# AuxBoard030610.net
KiCad netlist of a schematic drawn in Altium Designer
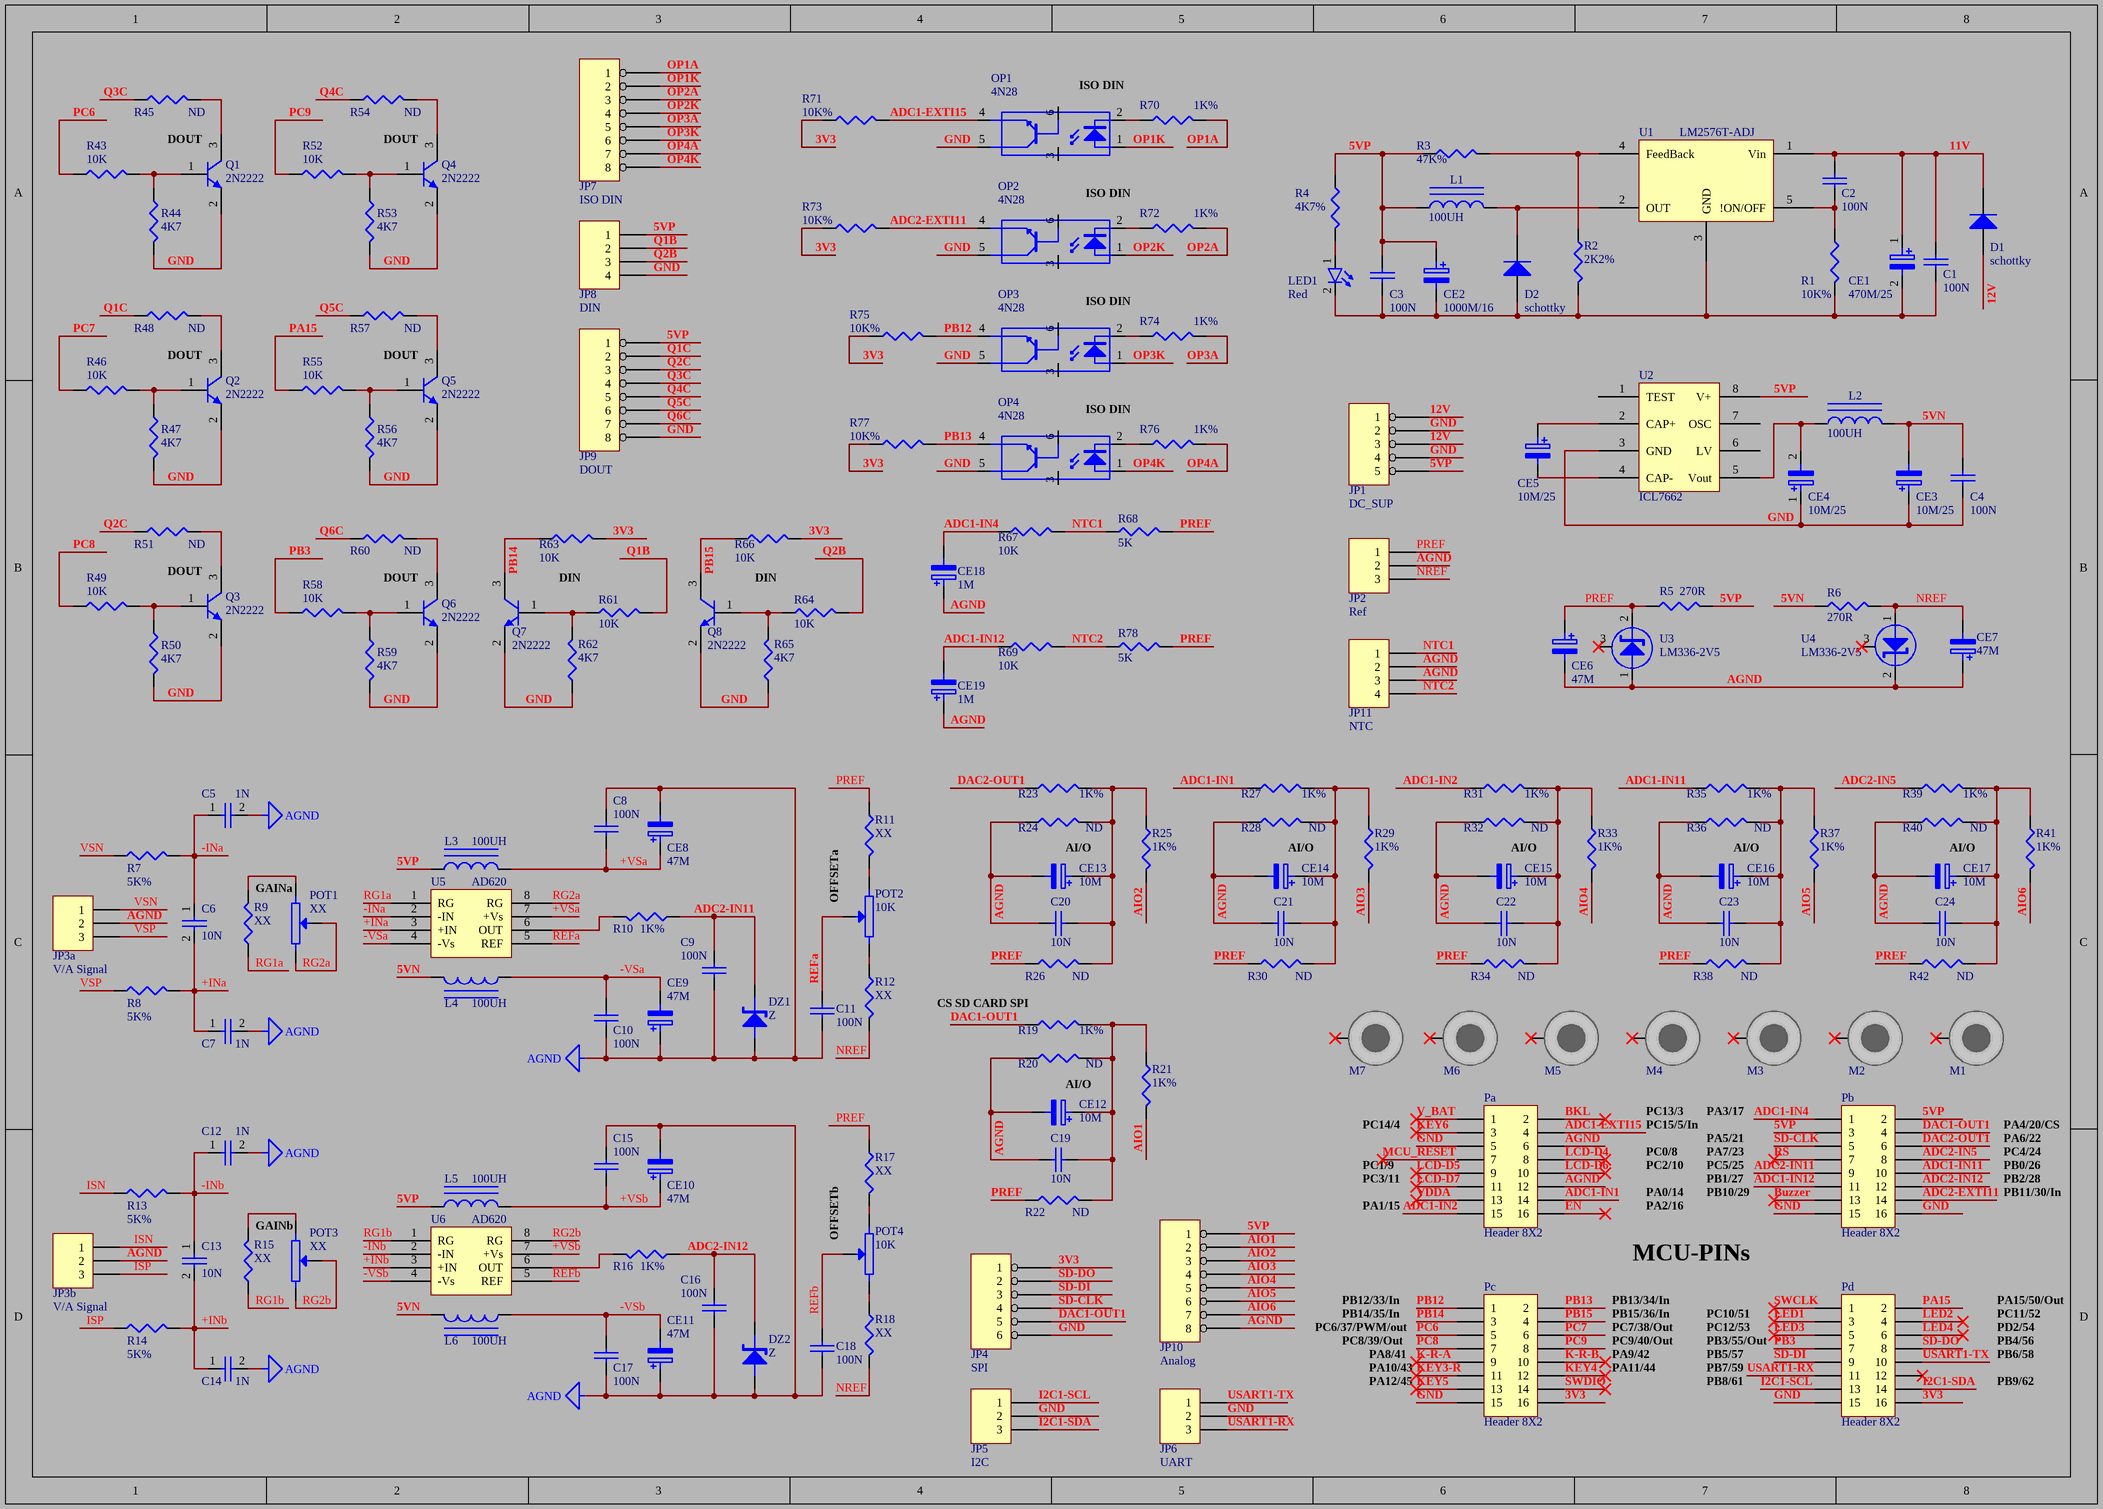
[diagram p0: AuxBoard030610.SchDoc]

(export (version "E")
  (design (tool "Eeschema 10.0.6"))
  (components
    (comp (ref "C1") (value "100N") (footprint "C2P") (libsource (lib "*") (part "C")))
    (comp (ref "C2") (value "100N") (footprint "SMD_CAP_1206.") (libsource (lib "*") (part "C")))
    (comp (ref "C3") (value "100N") (footprint "SMD_CAP_1206.") (libsource (lib "*") (part "C")))
    (comp (ref "C4") (value "100N") (footprint "SMD_CAP_1206.") (libsource (lib "*") (part "C")))
    (comp (ref "C5") (value "1N") (footprint "SMD_CAP_1206.") (libsource (lib "1402 Schlib 2020") (part "C")))
    (comp (ref "C6")
      (value "10N")
      (footprint "SMD_CAP_1206.")
      (libsource (lib "1402 Schlib 2020") (part "C"))
    )
    (comp (ref "C7") (value "1N") (footprint "SMD_CAP_1206.") (libsource (lib "1402 Schlib 2020") (part "C")))
    (comp (ref "C8")
      (value "100N")
      (footprint "SMD_CAP_1206.")
      (libsource (lib "1403 Schlib 2020") (part "C"))
    )
    (comp (ref "C9")
      (value "100N")
      (footprint "SMD_CAP_1206.")
      (libsource (lib "1403 Schlib 2020") (part "C"))
    )
    (comp (ref "C10")
      (value "100N")
      (footprint "SMD_CAP_1206.")
      (libsource (lib "1403 Schlib 2020") (part "C"))
    )
    (comp (ref "C11")
      (value "100N")
      (footprint "SMD_CAP_1206.")
      (libsource (lib "1403 Schlib 2020") (part "C"))
    )
    (comp (ref "C12")
      (value "1N")
      (footprint "SMD_CAP_1206.")
      (libsource (lib "1402 Schlib 2020") (part "C"))
    )
    (comp (ref "C13")
      (value "10N")
      (footprint "SMD_CAP_1206.")
      (libsource (lib "1402 Schlib 2020") (part "C"))
    )
    (comp (ref "C14")
      (value "1N")
      (footprint "SMD_CAP_1206.")
      (libsource (lib "1402 Schlib 2020") (part "C"))
    )
    (comp (ref "C15")
      (value "100N")
      (footprint "SMD_CAP_1206.")
      (libsource (lib "1403 Schlib 2020") (part "C"))
    )
    (comp (ref "C16")
      (value "100N")
      (footprint "SMD_CAP_1206.")
      (libsource (lib "1403 Schlib 2020") (part "C"))
    )
    (comp (ref "C17")
      (value "100N")
      (footprint "SMD_CAP_1206.")
      (libsource (lib "1403 Schlib 2020") (part "C"))
    )
    (comp (ref "C18")
      (value "100N")
      (footprint "SMD_CAP_1206.")
      (libsource (lib "1403 Schlib 2020") (part "C"))
    )
    (comp (ref "C19") (value "10N") (footprint "SMD_CAP_1206.") (libsource (lib "*") (part "C")))
    (comp (ref "C20") (value "10N") (footprint "SMD_CAP_1206.") (libsource (lib "*") (part "C")))
    (comp (ref "C21") (value "10N") (footprint "SMD_CAP_1206.") (libsource (lib "*") (part "C")))
    (comp (ref "C22") (value "10N") (footprint "SMD_CAP_1206.") (libsource (lib "*") (part "C")))
    (comp (ref "C23") (value "10N") (footprint "SMD_CAP_1206.") (libsource (lib "*") (part "C")))
    (comp (ref "C24") (value "10N") (footprint "SMD_CAP_1206.") (libsource (lib "*") (part "C")))
    (comp (ref "CE1") (value "470M/25") (footprint "CAP-E-6") (libsource (lib "") (part "E_1")))
    (comp (ref "CE2") (value "1000M/16") (footprint "CAP-E-6") (libsource (lib "*") (part "E")))
    (comp (ref "CE3") (value "10M/25") (footprint "CAP-E-3") (libsource (lib "*") (part "E")))
    (comp (ref "CE4") (value "10M/25") (footprint "CAP-E-3") (libsource (lib "") (part "E_1")))
    (comp (ref "CE5") (value "10M/25") (footprint "CAP-E-3") (libsource (lib "*") (part "E")))
    (comp (ref "CE6") (value "47M") (footprint "CAP-E-4") (libsource (lib "1403 Schlib 2020") (part "E")))
    (comp (ref "CE7") (value "47M") (footprint "CAP-E-4") (libsource (lib "1403 Schlib 2020") (part "E")))
    (comp (ref "CE8") (value "47M") (footprint "CAP-E-4") (libsource (lib "1403 Schlib 2020") (part "E")))
    (comp (ref "CE9") (value "47M") (footprint "CAP-E-4") (libsource (lib "1403 Schlib 2020") (part "E")))
    (comp (ref "CE10") (value "47M") (footprint "CAP-E-4") (libsource (lib "1403 Schlib 2020") (part "E")))
    (comp (ref "CE11") (value "47M") (footprint "CAP-E-4") (libsource (lib "1403 Schlib 2020") (part "E")))
    (comp (ref "CE12") (value "10M") (footprint "CAP-E-3") (libsource (lib "*") (part "E")))
    (comp (ref "CE13") (value "10M") (footprint "CAP-E-3") (libsource (lib "*") (part "E")))
    (comp (ref "CE14") (value "10M") (footprint "CAP-E-3") (libsource (lib "*") (part "E")))
    (comp (ref "CE15") (value "10M") (footprint "CAP-E-3") (libsource (lib "*") (part "E")))
    (comp (ref "CE16") (value "10M") (footprint "CAP-E-3") (libsource (lib "*") (part "E")))
    (comp (ref "CE17") (value "10M") (footprint "CAP-E-3") (libsource (lib "*") (part "E")))
    (comp (ref "CE18") (value "1M") (footprint "CAP-E-2") (libsource (lib "*") (part "E")))
    (comp (ref "CE19") (value "1M") (footprint "CAP-E-2") (libsource (lib "*") (part "E")))
    (comp (ref "D1")
      (value "schottky")
      (footprint "SMA-M")
      (description "Default Diode")
      (fields (field (name "PUBLISHER") "Altium Limited"))
      (libsource (lib "Miscellaneous Devices") (part "Diode"))
    )
    (comp (ref "D2")
      (value "schottky")
      (footprint "SMA-M")
      (description "Default Diode")
      (fields (field (name "PUBLISHER") "Altium Limited"))
      (libsource (lib "Miscellaneous Devices") (part "Diode"))
    )
    (comp (ref "DZ1") (value "Z") (footprint "D4P") (libsource (lib "1402 Schlib 2020") (part "Z")))
    (comp (ref "DZ2") (value "Z") (footprint "D4P") (libsource (lib "1402 Schlib 2020") (part "Z")))
    (comp (ref "JP1")
      (value "DC_SUP")
      (footprint "dsip 5 right")
      (libsource (lib "1402 Schlib 2020") (part "HEADER 5"))
    )
    (comp (ref "JP2")
      (value "Ref")
      (footprint "dsip 3 right")
      (description "Header, 3-Pin")
      (fields (field (name "PUBLISHER") "Altium Limited"))
      (libsource (lib "1402 Schlib 2020") (part "Header 3"))
    )
    (comp (ref "JP3a")
      (value "V/A Signal")
      (footprint "dsip 3 right")
      (description "Header, 3-Pin")
      (fields (field (name "PUBLISHER") "Altium Limited"))
      (libsource (lib "1402 Schlib 2020") (part "Header 3"))
    )
    (comp (ref "JP3b")
      (value "V/A Signal")
      (footprint "dsip 3 right")
      (description "Header, 3-Pin")
      (fields (field (name "PUBLISHER") "Altium Limited"))
      (libsource (lib "1402 Schlib 2020") (part "Header 3"))
    )
    (comp (ref "JP4")
      (value "SPI")
      (footprint "SIP 6 Right")
      (libsource (lib "1402 Schlib 2020") (part "HEADER 6"))
    )
    (comp (ref "JP5")
      (value "I2C")
      (footprint "SIP 3 Right")
      (description "Header, 3-Pin")
      (fields (field (name "PUBLISHER") "Altium Limited"))
      (libsource (lib "1402 Schlib 2020") (part "Header 3"))
    )
    (comp (ref "JP6")
      (value "UART")
      (footprint "SIP 3 Right")
      (description "Header, 3-Pin")
      (fields (field (name "PUBLISHER") "Altium Limited"))
      (libsource (lib "1402 Schlib 2020") (part "Header 3"))
    )
    (comp (ref "JP7")
      (value "ISO DIN")
      (footprint "dsip 8 right")
      (libsource (lib "1402 Schlib 2020") (part "HEADER 8"))
    )
    (comp (ref "JP8")
      (value "DIN")
      (footprint "dsip 4 right")
      (description "Header, 4-Pin")
      (fields (field (name "PUBLISHER") "Altium Limited"))
      (libsource (lib "1402 Schlib 2020") (part "Header 4"))
    )
    (comp (ref "JP9")
      (value "DOUT")
      (footprint "dsip 8 right")
      (libsource (lib "1402 Schlib 2020") (part "HEADER 8"))
    )
    (comp (ref "JP10")
      (value "Analog")
      (footprint "dsip 8 right")
      (libsource (lib "1402 Schlib 2020") (part "HEADER 8"))
    )
    (comp (ref "JP11")
      (value "NTC")
      (footprint "dsip 4 right")
      (description "Header, 4-Pin")
      (fields (field (name "PUBLISHER") "Altium Limited"))
      (libsource (lib "1402 Schlib 2020") (part "Header 4"))
    )
    (comp (ref "L1") (value "100UH") (footprint "INDUCTOR-ylw") (libsource (lib "") (part "INDUCTOR IRON_1")))
    (comp (ref "L2") (value "100UH") (footprint "r4p") (libsource (lib "") (part "INDUCTOR IRON_1")))
    (comp (ref "L3") (value "100UH") (footprint "r4p") (libsource (lib "") (part "INDUCTOR IRON_1")))
    (comp (ref "L4") (value "100UH") (footprint "r4p") (libsource (lib "*") (part "INDUCTOR IRON")))
    (comp (ref "L5") (value "100UH") (footprint "r4p") (libsource (lib "") (part "INDUCTOR IRON_1")))
    (comp (ref "L6") (value "100UH") (footprint "r4p") (libsource (lib "*") (part "INDUCTOR IRON")))
    (comp (ref "LED1")
      (value "Red")
      (footprint "LED_SMD_1206")
      (description "LED")
      (fields (field (name "COLOR") "Red") (field (name "DESIGNER") "Saeid Jorablo"))
      (libsource (lib "My Library") (part "LED"))
    )
    (comp (ref "M1")
      (value "Comment")
      (footprint "Stud-hole")
      (description "SCREW mouting, M1.6, 1.6mm diameter and 3.2mm PanHead")
      (libsource (lib "DotexGroup_LIB") (part "SCMH_M1P6"))
    )
    (comp (ref "M2")
      (value "Comment")
      (footprint "Stud-hole")
      (description "SCREW mouting, M1.6, 1.6mm diameter and 3.2mm PanHead")
      (libsource (lib "DotexGroup_LIB") (part "SCMH_M1P6"))
    )
    (comp (ref "M3")
      (value "Comment")
      (footprint "Stud-hole")
      (description "SCREW mouting, M1.6, 1.6mm diameter and 3.2mm PanHead")
      (libsource (lib "DotexGroup_LIB") (part "SCMH_M1P6"))
    )
    (comp (ref "M4")
      (value "Comment")
      (footprint "Stud-hole")
      (description "SCREW mouting, M1.6, 1.6mm diameter and 3.2mm PanHead")
      (libsource (lib "DotexGroup_LIB") (part "SCMH_M1P6"))
    )
    (comp (ref "M5")
      (value "Comment")
      (footprint "Stud-hole")
      (description "SCREW mouting, M1.6, 1.6mm diameter and 3.2mm PanHead")
      (libsource (lib "DotexGroup_LIB") (part "SCMH_M1P6"))
    )
    (comp (ref "M6")
      (value "Comment")
      (footprint "Stud-hole")
      (description "SCREW mouting, M1.6, 1.6mm diameter and 3.2mm PanHead")
      (libsource (lib "DotexGroup_LIB") (part "SCMH_M1P6"))
    )
    (comp (ref "M7")
      (value "Comment")
      (footprint "Stud-hole")
      (description "SCREW mouting, M1.6, 1.6mm diameter and 3.2mm PanHead")
      (libsource (lib "DotexGroup_LIB") (part "SCMH_M1P6"))
    )
    (comp (ref "OP1")
      (value "4N28")
      (footprint "DIP6")
      (libsource (lib "1402 Schlib 2020") (part "OPTODIP6"))
    )
    (comp (ref "OP2")
      (value "4N28")
      (footprint "DIP6")
      (libsource (lib "1402 Schlib 2020") (part "OPTODIP6"))
    )
    (comp (ref "OP3")
      (value "4N28")
      (footprint "DIP6")
      (libsource (lib "1402 Schlib 2020") (part "OPTODIP6"))
    )
    (comp (ref "OP4")
      (value "4N28")
      (footprint "DIP6")
      (libsource (lib "1402 Schlib 2020") (part "OPTODIP6"))
    )
    (comp (ref "Pa")
      (value "Header 8X2")
      (footprint "HDR2X8")
      (description "Header, 8-Pin, Dual row")
      (fields (field (name "PUBLISHER") "Altium Limited"))
      (libsource (lib "Miscellaneous Connectors") (part "Header 8X2"))
    )
    (comp (ref "Pb")
      (value "Header 8X2")
      (footprint "HDR2X8")
      (description "Header, 8-Pin, Dual row")
      (fields (field (name "PUBLISHER") "Altium Limited"))
      (libsource (lib "Miscellaneous Connectors") (part "Header 8X2"))
    )
    (comp (ref "Pc")
      (value "Header 8X2")
      (footprint "HDR2X8")
      (description "Header, 8-Pin, Dual row")
      (fields (field (name "PUBLISHER") "Altium Limited"))
      (libsource (lib "Miscellaneous Connectors") (part "Header 8X2"))
    )
    (comp (ref "Pd")
      (value "Header 8X2")
      (footprint "HDR2X8")
      (description "Header, 8-Pin, Dual row")
      (fields (field (name "PUBLISHER") "Altium Limited"))
      (libsource (lib "Miscellaneous Connectors") (part "Header 8X2"))
    )
    (comp (ref "POT1")
      (value "XX")
      (footprint "pot multi turn")
      (libsource (lib "1402 Schlib 2020") (part "POT2"))
    )
    (comp (ref "POT2")
      (value "10K")
      (footprint "pot multi turn")
      (libsource (lib "1402 Schlib 2020") (part "POT2"))
    )
    (comp (ref "POT3")
      (value "XX")
      (footprint "pot multi turn")
      (libsource (lib "1402 Schlib 2020") (part "POT2"))
    )
    (comp (ref "POT4")
      (value "10K")
      (footprint "pot multi turn")
      (libsource (lib "1402 Schlib 2020") (part "POT2"))
    )
    (comp (ref "Q1")
      (value "2N2222")
      (footprint "2N2222")
      (description "NPN")
      (fields (field (name "PUBLISHER") "Altium Limited"))
      (libsource (lib "1402 Schlib 2020") (part "1FW"))
    )
    (comp (ref "Q2")
      (value "2N2222")
      (footprint "2N2222")
      (description "NPN")
      (fields (field (name "PUBLISHER") "Altium Limited"))
      (libsource (lib "1402 Schlib 2020") (part "1FW"))
    )
    (comp (ref "Q3")
      (value "2N2222")
      (footprint "2N2222")
      (description "NPN")
      (fields (field (name "PUBLISHER") "Altium Limited"))
      (libsource (lib "1402 Schlib 2020") (part "1FW"))
    )
    (comp (ref "Q4")
      (value "2N2222")
      (footprint "2N2222")
      (description "NPN")
      (fields (field (name "PUBLISHER") "Altium Limited"))
      (libsource (lib "1402 Schlib 2020") (part "1FW"))
    )
    (comp (ref "Q5")
      (value "2N2222")
      (footprint "2N2222")
      (description "NPN")
      (fields (field (name "PUBLISHER") "Altium Limited"))
      (libsource (lib "1402 Schlib 2020") (part "1FW"))
    )
    (comp (ref "Q6")
      (value "2N2222")
      (footprint "2N2222")
      (description "NPN")
      (fields (field (name "PUBLISHER") "Altium Limited"))
      (libsource (lib "1402 Schlib 2020") (part "1FW"))
    )
    (comp (ref "Q7")
      (value "2N2222")
      (footprint "2N2222")
      (description "NPN")
      (fields (field (name "PUBLISHER") "Altium Limited"))
      (libsource (lib "1402 Schlib 2020") (part "1FW"))
    )
    (comp (ref "Q8")
      (value "2N2222")
      (footprint "2N2222")
      (description "NPN")
      (fields (field (name "PUBLISHER") "Altium Limited"))
      (libsource (lib "1402 Schlib 2020") (part "1FW"))
    )
    (comp (ref "R1") (value "10K%") (footprint "RES_1206") (libsource (lib "*") (part "R")))
    (comp (ref "R2") (value "2K2%") (footprint "RES_1206") (libsource (lib "*") (part "R")))
    (comp (ref "R3") (value "47K%") (footprint "RES_1206") (libsource (lib "*") (part "R")))
    (comp (ref "R4") (value "4K7%") (footprint "RES_1206") (libsource (lib "*") (part "R")))
    (comp (ref "R5") (value "270R") (footprint "RES_1206") (libsource (lib "*") (part "R")))
    (comp (ref "R6") (value "270R") (footprint "RES_1206") (libsource (lib "*") (part "R")))
    (comp (ref "R7") (value "5K%") (footprint "R4P") (libsource (lib "*") (part "R")))
    (comp (ref "R8") (value "5K%") (footprint "R4P") (libsource (lib "*") (part "R")))
    (comp (ref "R9") (value "XX") (footprint "R4P") (libsource (lib "*") (part "R")))
    (comp (ref "R10") (value "1K%") (footprint "RES_1206") (libsource (lib "*") (part "R")))
    (comp (ref "R11") (value "XX") (footprint "RES_1206") (libsource (lib "*") (part "R")))
    (comp (ref "R12") (value "XX") (footprint "RES_1206") (libsource (lib "*") (part "R")))
    (comp (ref "R13") (value "5K%") (footprint "R4P") (libsource (lib "*") (part "R")))
    (comp (ref "R14") (value "5K%") (footprint "R4P") (libsource (lib "*") (part "R")))
    (comp (ref "R15") (value "XX") (footprint "R4P") (libsource (lib "*") (part "R")))
    (comp (ref "R16") (value "1K%") (footprint "RES_1206") (libsource (lib "*") (part "R")))
    (comp (ref "R17") (value "XX") (footprint "RES_1206") (libsource (lib "*") (part "R")))
    (comp (ref "R18") (value "XX") (footprint "RES_1206") (libsource (lib "*") (part "R")))
    (comp (ref "R19") (value "1K%") (footprint "RES_1206") (libsource (lib "*") (part "R")))
    (comp (ref "R20") (value "ND") (footprint "RES_1206") (libsource (lib "*") (part "R")))
    (comp (ref "R21") (value "1K%") (footprint "RES_1206") (libsource (lib "*") (part "R")))
    (comp (ref "R22") (value "ND") (footprint "RES_1206") (libsource (lib "*") (part "R")))
    (comp (ref "R23") (value "1K%") (footprint "RES_1206") (libsource (lib "*") (part "R")))
    (comp (ref "R24") (value "ND") (footprint "RES_1206") (libsource (lib "*") (part "R")))
    (comp (ref "R25") (value "1K%") (footprint "RES_1206") (libsource (lib "*") (part "R")))
    (comp (ref "R26") (value "ND") (footprint "RES_1206") (libsource (lib "*") (part "R")))
    (comp (ref "R27") (value "1K%") (footprint "RES_1206") (libsource (lib "*") (part "R")))
    (comp (ref "R28") (value "ND") (footprint "RES_1206") (libsource (lib "*") (part "R")))
    (comp (ref "R29") (value "1K%") (footprint "RES_1206") (libsource (lib "*") (part "R")))
    (comp (ref "R30") (value "ND") (footprint "RES_1206") (libsource (lib "*") (part "R")))
    (comp (ref "R31") (value "1K%") (footprint "RES_1206") (libsource (lib "*") (part "R")))
    (comp (ref "R32") (value "ND") (footprint "RES_1206") (libsource (lib "*") (part "R")))
    (comp (ref "R33") (value "1K%") (footprint "RES_1206") (libsource (lib "*") (part "R")))
    (comp (ref "R34") (value "ND") (footprint "RES_1206") (libsource (lib "*") (part "R")))
    (comp (ref "R35") (value "1K%") (footprint "RES_1206") (libsource (lib "*") (part "R")))
    (comp (ref "R36") (value "ND") (footprint "RES_1206") (libsource (lib "*") (part "R")))
    (comp (ref "R37") (value "1K%") (footprint "RES_1206") (libsource (lib "*") (part "R")))
    (comp (ref "R38") (value "ND") (footprint "RES_1206") (libsource (lib "*") (part "R")))
    (comp (ref "R39") (value "1K%") (footprint "RES_1206") (libsource (lib "*") (part "R")))
    (comp (ref "R40") (value "ND") (footprint "RES_1206") (libsource (lib "*") (part "R")))
    (comp (ref "R41") (value "1K%") (footprint "RES_1206") (libsource (lib "*") (part "R")))
    (comp (ref "R42") (value "ND") (footprint "RES_1206") (libsource (lib "*") (part "R")))
    (comp (ref "R43") (value "10K") (footprint "RES_1206") (libsource (lib "*") (part "R")))
    (comp (ref "R44") (value "4K7") (footprint "RES_1206") (libsource (lib "*") (part "R")))
    (comp (ref "R45") (value "ND") (footprint "RES_1206") (libsource (lib "*") (part "R")))
    (comp (ref "R46") (value "10K") (footprint "RES_1206") (libsource (lib "*") (part "R")))
    (comp (ref "R47") (value "4K7") (footprint "RES_1206") (libsource (lib "*") (part "R")))
    (comp (ref "R48") (value "ND") (footprint "RES_1206") (libsource (lib "*") (part "R")))
    (comp (ref "R49") (value "10K") (footprint "RES_1206") (libsource (lib "*") (part "R")))
    (comp (ref "R50") (value "4K7") (footprint "RES_1206") (libsource (lib "*") (part "R")))
    (comp (ref "R51") (value "ND") (footprint "RES_1206") (libsource (lib "*") (part "R")))
    (comp (ref "R52") (value "10K") (footprint "RES_1206") (libsource (lib "*") (part "R")))
    (comp (ref "R53") (value "4K7") (footprint "RES_1206") (libsource (lib "*") (part "R")))
    (comp (ref "R54") (value "ND") (footprint "RES_1206") (libsource (lib "*") (part "R")))
    (comp (ref "R55") (value "10K") (footprint "RES_1206") (libsource (lib "*") (part "R")))
    (comp (ref "R56") (value "4K7") (footprint "RES_1206") (libsource (lib "*") (part "R")))
    (comp (ref "R57") (value "ND") (footprint "RES_1206") (libsource (lib "*") (part "R")))
    (comp (ref "R58") (value "10K") (footprint "RES_1206") (libsource (lib "*") (part "R")))
    (comp (ref "R59") (value "4K7") (footprint "RES_1206") (libsource (lib "*") (part "R")))
    (comp (ref "R60") (value "ND") (footprint "RES_1206") (libsource (lib "*") (part "R")))
    (comp (ref "R61") (value "10K") (footprint "RES_1206") (libsource (lib "*") (part "R")))
    (comp (ref "R62") (value "4K7") (footprint "RES_1206") (libsource (lib "*") (part "R")))
    (comp (ref "R63") (value "10K") (footprint "RES_1206") (libsource (lib "*") (part "R")))
    (comp (ref "R64") (value "10K") (footprint "RES_1206") (libsource (lib "*") (part "R")))
    (comp (ref "R65") (value "4K7") (footprint "RES_1206") (libsource (lib "*") (part "R")))
    (comp (ref "R66") (value "10K") (footprint "RES_1206") (libsource (lib "*") (part "R")))
    (comp (ref "R67") (value "10K") (footprint "RES_1206") (libsource (lib "*") (part "R")))
    (comp (ref "R68") (value "5K") (footprint "RES_1206") (libsource (lib "*") (part "R")))
    (comp (ref "R69") (value "10K") (footprint "RES_1206") (libsource (lib "*") (part "R")))
    (comp (ref "R70") (value "1K%") (footprint "RES_1206") (libsource (lib "*") (part "R")))
    (comp (ref "R71") (value "10K%") (footprint "RES_1206") (libsource (lib "*") (part "R")))
    (comp (ref "R72") (value "1K%") (footprint "RES_1206") (libsource (lib "*") (part "R")))
    (comp (ref "R73") (value "10K%") (footprint "RES_1206") (libsource (lib "*") (part "R")))
    (comp (ref "R74") (value "1K%") (footprint "RES_1206") (libsource (lib "*") (part "R")))
    (comp (ref "R75") (value "10K%") (footprint "RES_1206") (libsource (lib "*") (part "R")))
    (comp (ref "R76") (value "1K%") (footprint "RES_1206") (libsource (lib "*") (part "R")))
    (comp (ref "R77") (value "10K%") (footprint "RES_1206") (libsource (lib "*") (part "R")))
    (comp (ref "R78") (value "5K") (footprint "RES_1206") (libsource (lib "*") (part "R")))
    (comp (ref "U1") (value "LM2576T-ADJ") (footprint "D2PACK_TO263-5") (libsource (lib "*") (part "LM2576")))
    (comp (ref "U2")
      (value "ICL7662")
      (footprint "DIP8")
      (libsource (lib "1402 Schlib 2020") (part "ICL7662"))
    )
    (comp (ref "U3")
      (value "LM336-2V5")
      (footprint "lm336")
      (libsource (lib "1403 Schlib 2020") (part "LM336"))
    )
    (comp (ref "U4")
      (value "LM336-2V5")
      (footprint "lm336")
      (libsource (lib "1403 Schlib 2020") (part "LM336"))
    )
    (comp (ref "U5") (value "AD620") (footprint "DIP8") (libsource (lib "1402 Schlib 2020") (part "AD620")))
    (comp (ref "U6") (value "AD620") (footprint "DIP8") (libsource (lib "1402 Schlib 2020") (part "AD620")))
  )
  (nets
    (net (code "1") (name "/+INa") (class "Default")
      (node (ref "C6") (pin "2") (pintype "passive"))
      (node (ref "C7") (pin "1") (pintype "passive"))
      (node (ref "R8") (pin "2") (pintype "passive"))
      (node (ref "U5") (pin "3") (pinfunction "+IN_3") (pintype "passive"))
    )
    (net (code "2") (name "/+INb") (class "Default")
      (node (ref "C13") (pin "2") (pintype "passive"))
      (node (ref "C14") (pin "1") (pintype "passive"))
      (node (ref "R14") (pin "2") (pintype "passive"))
      (node (ref "U6") (pin "3") (pinfunction "+IN_3") (pintype "passive"))
    )
    (net (code "3") (name "/+VSa") (class "Default")
      (node (ref "C8") (pin "2") (pintype "passive"))
      (node (ref "CE8") (pin "1") (pintype "passive"))
      (node (ref "L3") (pin "2") (pinfunction "2_2") (pintype "passive"))
      (node (ref "U5") (pin "7") (pinfunction "+Vs_7") (pintype "passive"))
    )
    (net (code "4") (name "/+VSb") (class "Default")
      (node (ref "C15") (pin "2") (pintype "passive"))
      (node (ref "CE10") (pin "1") (pintype "passive"))
      (node (ref "L5") (pin "2") (pinfunction "2_2") (pintype "passive"))
      (node (ref "U6") (pin "7") (pinfunction "+Vs_7") (pintype "passive"))
    )
    (net (code "5") (name "/-INa") (class "Default")
      (node (ref "C5") (pin "1") (pintype "passive"))
      (node (ref "C6") (pin "1") (pintype "passive"))
      (node (ref "R7") (pin "2") (pintype "passive"))
      (node (ref "U5") (pin "2") (pinfunction "-IN_2") (pintype "passive"))
    )
    (net (code "6") (name "/-INb") (class "Default")
      (node (ref "C12") (pin "1") (pintype "passive"))
      (node (ref "C13") (pin "1") (pintype "passive"))
      (node (ref "R13") (pin "2") (pintype "passive"))
      (node (ref "U6") (pin "2") (pinfunction "-IN_2") (pintype "passive"))
    )
    (net (code "7") (name "/-VSa") (class "Default")
      (node (ref "C10") (pin "1") (pintype "passive"))
      (node (ref "CE9") (pin "2") (pintype "passive"))
      (node (ref "L4") (pin "2") (pinfunction "2_2") (pintype "passive"))
      (node (ref "U5") (pin "4") (pinfunction "-Vs_4") (pintype "passive"))
    )
    (net (code "8") (name "/-VSb") (class "Default")
      (node (ref "C17") (pin "1") (pintype "passive"))
      (node (ref "CE11") (pin "2") (pintype "passive"))
      (node (ref "L6") (pin "2") (pinfunction "2_2") (pintype "passive"))
      (node (ref "U6") (pin "4") (pinfunction "-Vs_4") (pintype "passive"))
    )
    (net (code "9") (name "/3V3") (class "Default")
      (node (ref "JP4") (pin "1") (pinfunction "1_1") (pintype "passive"))
      (node (ref "Pc") (pin "16") (pinfunction "16_16") (pintype "passive"))
      (node (ref "Pd") (pin "16") (pinfunction "16_16") (pintype "passive"))
      (node (ref "R63") (pin "1") (pintype "passive"))
      (node (ref "R66") (pin "1") (pintype "passive"))
      (node (ref "R71") (pin "2") (pintype "passive"))
      (node (ref "R73") (pin "2") (pintype "passive"))
      (node (ref "R75") (pin "2") (pintype "passive"))
      (node (ref "R77") (pin "2") (pintype "passive"))
    )
    (net (code "10") (name "/5VN") (class "Default")
      (node (ref "C4") (pin "1") (pintype "passive"))
      (node (ref "CE3") (pin "2") (pintype "passive"))
      (node (ref "L2") (pin "2") (pinfunction "2_2") (pintype "passive"))
      (node (ref "L4") (pin "1") (pinfunction "1_1") (pintype "passive"))
      (node (ref "L6") (pin "1") (pinfunction "1_1") (pintype "passive"))
      (node (ref "R6") (pin "2") (pintype "passive"))
    )
    (net (code "11") (name "/5VP") (class "Default")
      (node (ref "C3") (pin "1") (pintype "passive"))
      (node (ref "CE2") (pin "1") (pintype "passive"))
      (node (ref "JP1") (pin "5") (pinfunction "5_5") (pintype "passive"))
      (node (ref "JP10") (pin "1") (pinfunction "1_1") (pintype "passive"))
      (node (ref "JP8") (pin "1") (pinfunction "1_1") (pintype "passive"))
      (node (ref "JP9") (pin "1") (pinfunction "1_1") (pintype "passive"))
      (node (ref "L1") (pin "1") (pinfunction "1_1") (pintype "passive"))
      (node (ref "L3") (pin "1") (pinfunction "1_1") (pintype "passive"))
      (node (ref "L5") (pin "1") (pinfunction "1_1") (pintype "passive"))
      (node (ref "Pb") (pin "2") (pinfunction "2_2") (pintype "passive"))
      (node (ref "Pb") (pin "3") (pinfunction "3_3") (pintype "passive"))
      (node (ref "R3") (pin "1") (pintype "passive"))
      (node (ref "R4") (pin "1") (pintype "passive"))
      (node (ref "R5") (pin "2") (pintype "passive"))
      (node (ref "U2") (pin "8") (pinfunction "V+_8") (pintype "passive"))
    )
    (net (code "12") (name "/11V") (class "Default")
      (node (ref "C1") (pin "1") (pintype "passive"))
      (node (ref "C2") (pin "1") (pintype "passive"))
      (node (ref "CE1") (pin "1") (pintype "passive"))
      (node (ref "D1") (pin "2") (pinfunction "K_2") (pintype "passive"))
      (node (ref "U1") (pin "1") (pinfunction "Vin_1") (pintype "passive"))
    )
    (net (code "13") (name "/12V") (class "Default")
      (node (ref "D1") (pin "1") (pinfunction "A_1") (pintype "passive"))
      (node (ref "JP1") (pin "1") (pinfunction "1_1") (pintype "passive"))
      (node (ref "JP1") (pin "3") (pinfunction "3_3") (pintype "passive"))
    )
    (net (code "14") (name "/ADC1-EXTI15") (class "Default")
      (node (ref "OP1") (pin "4") (pinfunction "E_4") (pintype "passive"))
      (node (ref "Pa") (pin "4") (pinfunction "4_4") (pintype "passive"))
      (node (ref "R71") (pin "1") (pintype "passive"))
    )
    (net (code "15") (name "/ADC1-IN1") (class "Default")
      (node (ref "Pa") (pin "14") (pinfunction "14_14") (pintype "passive"))
      (node (ref "R27") (pin "1") (pintype "passive"))
    )
    (net (code "16") (name "/ADC1-IN2") (class "Default")
      (node (ref "Pa") (pin "15") (pinfunction "15_15") (pintype "passive"))
      (node (ref "R31") (pin "1") (pintype "passive"))
    )
    (net (code "17") (name "/ADC1-IN4") (class "Default")
      (node (ref "CE18") (pin "2") (pintype "passive"))
      (node (ref "Pb") (pin "1") (pinfunction "1_1") (pintype "passive"))
      (node (ref "R67") (pin "2") (pintype "passive"))
    )
    (net (code "18") (name "/ADC1-IN11") (class "Default")
      (node (ref "Pb") (pin "10") (pinfunction "10_10") (pintype "passive"))
      (node (ref "R35") (pin "1") (pintype "passive"))
    )
    (net (code "19") (name "/ADC1-IN12") (class "Default")
      (node (ref "CE19") (pin "2") (pintype "passive"))
      (node (ref "Pb") (pin "11") (pinfunction "11_11") (pintype "passive"))
      (node (ref "R69") (pin "2") (pintype "passive"))
    )
    (net (code "20") (name "/ADC2-EXTI11") (class "Default")
      (node (ref "OP2") (pin "4") (pinfunction "E_4") (pintype "passive"))
      (node (ref "Pb") (pin "14") (pinfunction "14_14") (pintype "passive"))
      (node (ref "R73") (pin "1") (pintype "passive"))
    )
    (net (code "21") (name "/ADC2-IN5") (class "Default")
      (node (ref "Pb") (pin "8") (pinfunction "8_8") (pintype "passive"))
      (node (ref "R39") (pin "1") (pintype "passive"))
    )
    (net (code "22") (name "/ADC2-IN11") (class "Default")
      (node (ref "C9") (pin "1") (pintype "passive"))
      (node (ref "DZ1") (pin "2") (pinfunction "K_2") (pintype "passive"))
      (node (ref "Pb") (pin "9") (pinfunction "9_9") (pintype "passive"))
      (node (ref "R10") (pin "1") (pintype "passive"))
    )
    (net (code "23") (name "/ADC2-IN12") (class "Default")
      (node (ref "C16") (pin "1") (pintype "passive"))
      (node (ref "DZ2") (pin "2") (pinfunction "K_2") (pintype "passive"))
      (node (ref "Pb") (pin "12") (pinfunction "12_12") (pintype "passive"))
      (node (ref "R16") (pin "1") (pintype "passive"))
    )
    (net (code "24") (name "/AIO1") (class "Default")
      (node (ref "JP10") (pin "2") (pinfunction "2_2") (pintype "passive"))
      (node (ref "R21") (pin "2") (pintype "passive"))
    )
    (net (code "25") (name "/AIO2") (class "Default")
      (node (ref "JP10") (pin "3") (pinfunction "3_3") (pintype "passive"))
      (node (ref "R25") (pin "2") (pintype "passive"))
    )
    (net (code "26") (name "/AIO3") (class "Default")
      (node (ref "JP10") (pin "4") (pinfunction "4_4") (pintype "passive"))
      (node (ref "R29") (pin "2") (pintype "passive"))
    )
    (net (code "27") (name "/AIO4") (class "Default")
      (node (ref "JP10") (pin "5") (pinfunction "5_5") (pintype "passive"))
      (node (ref "R33") (pin "2") (pintype "passive"))
    )
    (net (code "28") (name "/AIO5") (class "Default")
      (node (ref "JP10") (pin "6") (pinfunction "6_6") (pintype "passive"))
      (node (ref "R37") (pin "2") (pintype "passive"))
    )
    (net (code "29") (name "/AIO6") (class "Default")
      (node (ref "JP10") (pin "7") (pinfunction "7_7") (pintype "passive"))
      (node (ref "R41") (pin "2") (pintype "passive"))
    )
    (net (code "30") (name "/BKL") (class "Default")
      (node (ref "Pa") (pin "2") (pinfunction "2_2") (pintype "passive+no_connect"))
    )
    (net (code "31") (name "/Buzzer") (class "Default")
      (node (ref "Pb") (pin "13") (pinfunction "13_13") (pintype "passive+no_connect"))
    )
    (net (code "32") (name "/DAC1-OUT1") (class "Default")
      (node (ref "JP4") (pin "5") (pinfunction "5_5") (pintype "passive"))
      (node (ref "Pb") (pin "4") (pinfunction "4_4") (pintype "passive"))
      (node (ref "R19") (pin "1") (pintype "passive"))
    )
    (net (code "33") (name "/DAC2-OUT1") (class "Default")
      (node (ref "Pb") (pin "6") (pinfunction "6_6") (pintype "passive"))
      (node (ref "R23") (pin "1") (pintype "passive"))
    )
    (net (code "34") (name "/EN") (class "Default")
      (node (ref "Pa") (pin "16") (pinfunction "16_16") (pintype "passive+no_connect"))
    )
    (net (code "35") (name "/GND") (class "Default")
      (node (ref "C4") (pin "2") (pintype "passive"))
      (node (ref "CE3") (pin "1") (pintype "passive"))
      (node (ref "CE4") (pin "1") (pintype "passive"))
      (node (ref "JP1") (pin "2") (pinfunction "2_2") (pintype "passive"))
      (node (ref "JP1") (pin "4") (pinfunction "4_4") (pintype "passive"))
      (node (ref "JP4") (pin "6") (pinfunction "6_6") (pintype "passive"))
      (node (ref "JP5") (pin "2") (pinfunction "2_2") (pintype "passive"))
      (node (ref "JP6") (pin "2") (pinfunction "2_2") (pintype "passive"))
      (node (ref "JP8") (pin "4") (pinfunction "4_4") (pintype "passive"))
      (node (ref "JP9") (pin "8") (pinfunction "8_8") (pintype "passive"))
      (node (ref "OP1") (pin "5") (pinfunction "C_5") (pintype "passive"))
      (node (ref "OP2") (pin "5") (pinfunction "C_5") (pintype "passive"))
      (node (ref "OP3") (pin "5") (pinfunction "C_5") (pintype "passive"))
      (node (ref "OP4") (pin "5") (pinfunction "C_5") (pintype "passive"))
      (node (ref "Pa") (pin "5") (pinfunction "5_5") (pintype "passive"))
      (node (ref "Pb") (pin "15") (pinfunction "15_15") (pintype "passive"))
      (node (ref "Pb") (pin "16") (pinfunction "16_16") (pintype "passive"))
      (node (ref "Pc") (pin "15") (pinfunction "15_15") (pintype "passive"))
      (node (ref "Pd") (pin "15") (pinfunction "15_15") (pintype "passive"))
      (node (ref "Q1") (pin "2") (pinfunction "E_2") (pintype "passive"))
      (node (ref "Q2") (pin "2") (pinfunction "E_2") (pintype "passive"))
      (node (ref "Q3") (pin "2") (pinfunction "E_2") (pintype "passive"))
      (node (ref "Q4") (pin "2") (pinfunction "E_2") (pintype "passive"))
      (node (ref "Q5") (pin "2") (pinfunction "E_2") (pintype "passive"))
      (node (ref "Q6") (pin "2") (pinfunction "E_2") (pintype "passive"))
      (node (ref "Q7") (pin "2") (pinfunction "E_2") (pintype "passive"))
      (node (ref "Q8") (pin "2") (pinfunction "E_2") (pintype "passive"))
      (node (ref "R44") (pin "2") (pintype "passive"))
      (node (ref "R47") (pin "2") (pintype "passive"))
      (node (ref "R50") (pin "2") (pintype "passive"))
      (node (ref "R53") (pin "2") (pintype "passive"))
      (node (ref "R56") (pin "2") (pintype "passive"))
      (node (ref "R59") (pin "2") (pintype "passive"))
      (node (ref "R62") (pin "2") (pintype "passive"))
      (node (ref "R65") (pin "2") (pintype "passive"))
      (node (ref "U2") (pin "3") (pinfunction "GND_3") (pintype "passive"))
    )
    (net (code "36") (name "/I2C1-SCL") (class "Default")
      (node (ref "JP5") (pin "1") (pinfunction "1_1") (pintype "passive"))
      (node (ref "Pd") (pin "13") (pinfunction "13_13") (pintype "passive"))
    )
    (net (code "37") (name "/I2C1-SDA") (class "Default")
      (node (ref "JP5") (pin "3") (pinfunction "3_3") (pintype "passive"))
      (node (ref "Pd") (pin "14") (pinfunction "14_14") (pintype "passive"))
    )
    (net (code "38") (name "/ISN") (class "Default")
      (node (ref "JP3b") (pin "1") (pinfunction "1_1") (pintype "passive"))
      (node (ref "R13") (pin "1") (pintype "passive"))
    )
    (net (code "39") (name "/ISP") (class "Default")
      (node (ref "JP3b") (pin "3") (pinfunction "3_3") (pintype "passive"))
      (node (ref "R14") (pin "1") (pintype "passive"))
    )
    (net (code "40") (name "/K-R-A") (class "Default")
      (node (ref "Pc") (pin "9") (pinfunction "9_9") (pintype "passive+no_connect"))
    )
    (net (code "41") (name "/K-R-B") (class "Default")
      (node (ref "Pc") (pin "10") (pinfunction "10_10") (pintype "passive+no_connect"))
    )
    (net (code "42") (name "/KEY3-R") (class "Default")
      (node (ref "Pc") (pin "11") (pinfunction "11_11") (pintype "passive+no_connect"))
    )
    (net (code "43") (name "/KEY4") (class "Default")
      (node (ref "Pc") (pin "12") (pinfunction "12_12") (pintype "passive+no_connect"))
    )
    (net (code "44") (name "/KEY5") (class "Default")
      (node (ref "Pc") (pin "13") (pinfunction "13_13") (pintype "passive+no_connect"))
    )
    (net (code "45") (name "/KEY6") (class "Default")
      (node (ref "Pa") (pin "3") (pinfunction "3_3") (pintype "passive+no_connect"))
    )
    (net (code "46") (name "/LCD-D4") (class "Default")
      (node (ref "Pa") (pin "8") (pinfunction "8_8") (pintype "passive+no_connect"))
    )
    (net (code "47") (name "/LCD-D5") (class "Default")
      (node (ref "Pa") (pin "9") (pinfunction "9_9") (pintype "passive+no_connect"))
    )
    (net (code "48") (name "/LCD-D6") (class "Default")
      (node (ref "Pa") (pin "10") (pinfunction "10_10") (pintype "passive+no_connect"))
    )
    (net (code "49") (name "/LCD-D7") (class "Default")
      (node (ref "Pa") (pin "11") (pinfunction "11_11") (pintype "passive+no_connect"))
    )
    (net (code "50") (name "/LED1") (class "Default")
      (node (ref "Pd") (pin "3") (pinfunction "3_3") (pintype "passive+no_connect"))
    )
    (net (code "51") (name "/LED2") (class "Default")
      (node (ref "Pd") (pin "4") (pinfunction "4_4") (pintype "passive+no_connect"))
    )
    (net (code "52") (name "/LED3") (class "Default")
      (node (ref "Pd") (pin "5") (pinfunction "5_5") (pintype "passive+no_connect"))
    )
    (net (code "53") (name "/LED4") (class "Default")
      (node (ref "Pd") (pin "6") (pinfunction "6_6") (pintype "passive+no_connect"))
    )
    (net (code "55") (name "/NREF") (class "Default")
      (node (ref "CE7") (pin "2") (pintype "passive"))
      (node (ref "JP2") (pin "3") (pinfunction "3_3") (pintype "passive"))
      (node (ref "R12") (pin "2") (pintype "passive"))
      (node (ref "R18") (pin "2") (pintype "passive"))
      (node (ref "R6") (pin "1") (pintype "passive"))
      (node (ref "U4") (pin "1") (pintype "passive"))
    )
    (net (code "56") (name "/NTC1") (class "Default")
      (node (ref "JP11") (pin "1") (pinfunction "1_1") (pintype "passive"))
      (node (ref "R67") (pin "1") (pintype "passive"))
      (node (ref "R68") (pin "2") (pintype "passive"))
    )
    (net (code "57") (name "/NTC2") (class "Default")
      (node (ref "JP11") (pin "4") (pinfunction "4_4") (pintype "passive"))
      (node (ref "R69") (pin "1") (pintype "passive"))
      (node (ref "R78") (pin "2") (pintype "passive"))
    )
    (net (code "58") (name "/OP1A") (class "Default")
      (node (ref "JP7") (pin "1") (pinfunction "1_1") (pintype "passive"))
      (node (ref "R70") (pin "1") (pintype "passive"))
    )
    (net (code "59") (name "/OP1K") (class "Default")
      (node (ref "JP7") (pin "2") (pinfunction "2_2") (pintype "passive"))
      (node (ref "OP1") (pin "1") (pinfunction "A_1") (pintype "passive"))
    )
    (net (code "60") (name "/OP2A") (class "Default")
      (node (ref "JP7") (pin "3") (pinfunction "3_3") (pintype "passive"))
      (node (ref "R72") (pin "1") (pintype "passive"))
    )
    (net (code "61") (name "/OP2K") (class "Default")
      (node (ref "JP7") (pin "4") (pinfunction "4_4") (pintype "passive"))
      (node (ref "OP2") (pin "1") (pinfunction "A_1") (pintype "passive"))
    )
    (net (code "62") (name "/OP3A") (class "Default")
      (node (ref "JP7") (pin "5") (pinfunction "5_5") (pintype "passive"))
      (node (ref "R74") (pin "1") (pintype "passive"))
    )
    (net (code "63") (name "/OP3K") (class "Default")
      (node (ref "JP7") (pin "6") (pinfunction "6_6") (pintype "passive"))
      (node (ref "OP3") (pin "1") (pinfunction "A_1") (pintype "passive"))
    )
    (net (code "64") (name "/OP4A") (class "Default")
      (node (ref "JP7") (pin "7") (pinfunction "7_7") (pintype "passive"))
      (node (ref "R76") (pin "1") (pintype "passive"))
    )
    (net (code "65") (name "/OP4K") (class "Default")
      (node (ref "JP7") (pin "8") (pinfunction "8_8") (pintype "passive"))
      (node (ref "OP4") (pin "1") (pinfunction "A_1") (pintype "passive"))
    )
    (net (code "66") (name "/PA15") (class "Default")
      (node (ref "Pd") (pin "2") (pinfunction "2_2") (pintype "passive"))
      (node (ref "R55") (pin "1") (pintype "passive"))
    )
    (net (code "67") (name "/PB3") (class "Default")
      (node (ref "Pd") (pin "7") (pinfunction "7_7") (pintype "passive"))
      (node (ref "R58") (pin "1") (pintype "passive"))
    )
    (net (code "68") (name "/PB12") (class "Default")
      (node (ref "OP3") (pin "4") (pinfunction "E_4") (pintype "passive"))
      (node (ref "Pc") (pin "1") (pinfunction "1_1") (pintype "passive"))
      (node (ref "R75") (pin "1") (pintype "passive"))
    )
    (net (code "69") (name "/PB13") (class "Default")
      (node (ref "OP4") (pin "4") (pinfunction "E_4") (pintype "passive"))
      (node (ref "Pc") (pin "2") (pinfunction "2_2") (pintype "passive"))
      (node (ref "R77") (pin "1") (pintype "passive"))
    )
    (net (code "70") (name "/PB14") (class "Default")
      (node (ref "Pc") (pin "3") (pinfunction "3_3") (pintype "passive"))
      (node (ref "Q7") (pin "3") (pinfunction "C_3") (pintype "passive"))
      (node (ref "R63") (pin "2") (pintype "passive"))
    )
    (net (code "71") (name "/PB15") (class "Default")
      (node (ref "Pc") (pin "4") (pinfunction "4_4") (pintype "passive"))
      (node (ref "Q8") (pin "3") (pinfunction "C_3") (pintype "passive"))
      (node (ref "R66") (pin "2") (pintype "passive"))
    )
    (net (code "72") (name "/PC6") (class "Default")
      (node (ref "Pc") (pin "5") (pinfunction "5_5") (pintype "passive"))
      (node (ref "R43") (pin "1") (pintype "passive"))
    )
    (net (code "73") (name "/PC7") (class "Default")
      (node (ref "Pc") (pin "6") (pinfunction "6_6") (pintype "passive"))
      (node (ref "R46") (pin "1") (pintype "passive"))
    )
    (net (code "74") (name "/PC8") (class "Default")
      (node (ref "Pc") (pin "7") (pinfunction "7_7") (pintype "passive"))
      (node (ref "R49") (pin "1") (pintype "passive"))
    )
    (net (code "75") (name "/PC9") (class "Default")
      (node (ref "Pc") (pin "8") (pinfunction "8_8") (pintype "passive"))
      (node (ref "R52") (pin "1") (pintype "passive"))
    )
    (net (code "76") (name "/PREF") (class "Default")
      (node (ref "CE6") (pin "1") (pintype "passive"))
      (node (ref "JP2") (pin "1") (pinfunction "1_1") (pintype "passive"))
      (node (ref "R11") (pin "1") (pintype "passive"))
      (node (ref "R17") (pin "1") (pintype "passive"))
      (node (ref "R22") (pin "1") (pintype "passive"))
      (node (ref "R26") (pin "1") (pintype "passive"))
      (node (ref "R30") (pin "1") (pintype "passive"))
      (node (ref "R34") (pin "1") (pintype "passive"))
      (node (ref "R38") (pin "1") (pintype "passive"))
      (node (ref "R42") (pin "1") (pintype "passive"))
      (node (ref "R5") (pin "1") (pintype "passive"))
      (node (ref "R68") (pin "1") (pintype "passive"))
      (node (ref "R78") (pin "1") (pintype "passive"))
      (node (ref "U3") (pin "2") (pintype "passive"))
    )
    (net (code "77") (name "/Q1B") (class "Default")
      (node (ref "JP8") (pin "2") (pinfunction "2_2") (pintype "passive"))
      (node (ref "R61") (pin "1") (pintype "passive"))
    )
    (net (code "78") (name "/Q1C") (class "Default")
      (node (ref "JP9") (pin "2") (pinfunction "2_2") (pintype "passive"))
      (node (ref "R48") (pin "2") (pintype "passive"))
    )
    (net (code "79") (name "/Q2B") (class "Default")
      (node (ref "JP8") (pin "3") (pinfunction "3_3") (pintype "passive"))
      (node (ref "R64") (pin "1") (pintype "passive"))
    )
    (net (code "80") (name "/Q2C") (class "Default")
      (node (ref "JP9") (pin "3") (pinfunction "3_3") (pintype "passive"))
      (node (ref "R51") (pin "2") (pintype "passive"))
    )
    (net (code "81") (name "/Q3C") (class "Default")
      (node (ref "JP9") (pin "4") (pinfunction "4_4") (pintype "passive"))
      (node (ref "R45") (pin "2") (pintype "passive"))
    )
    (net (code "82") (name "/Q4C") (class "Default")
      (node (ref "JP9") (pin "5") (pinfunction "5_5") (pintype "passive"))
      (node (ref "R54") (pin "2") (pintype "passive"))
    )
    (net (code "83") (name "/Q5C") (class "Default")
      (node (ref "JP9") (pin "6") (pinfunction "6_6") (pintype "passive"))
      (node (ref "R57") (pin "2") (pintype "passive"))
    )
    (net (code "84") (name "/Q6C") (class "Default")
      (node (ref "JP9") (pin "7") (pinfunction "7_7") (pintype "passive"))
      (node (ref "R60") (pin "2") (pintype "passive"))
    )
    (net (code "85") (name "/REFa") (class "Default")
      (node (ref "C11") (pin "1") (pintype "passive"))
      (node (ref "POT2") (pin "3") (pintype "passive"))
      (node (ref "U5") (pin "5") (pinfunction "REF_5") (pintype "passive"))
    )
    (net (code "86") (name "/REFb") (class "Default")
      (node (ref "C18") (pin "1") (pintype "passive"))
      (node (ref "POT4") (pin "3") (pintype "passive"))
      (node (ref "U6") (pin "5") (pinfunction "REF_5") (pintype "passive"))
    )
    (net (code "87") (name "/RG1a") (class "Default")
      (node (ref "R9") (pin "1") (pintype "passive"))
      (node (ref "U5") (pin "1") (pinfunction "RG_1") (pintype "passive"))
    )
    (net (code "88") (name "/RG1b") (class "Default")
      (node (ref "R15") (pin "1") (pintype "passive"))
      (node (ref "U6") (pin "1") (pinfunction "RG_1") (pintype "passive"))
    )
    (net (code "89") (name "/RG2a") (class "Default")
      (node (ref "POT1") (pin "2") (pintype "passive"))
      (node (ref "POT1") (pin "3") (pintype "passive"))
      (node (ref "U5") (pin "8") (pinfunction "RG_8") (pintype "passive"))
    )
    (net (code "90") (name "/RG2b") (class "Default")
      (node (ref "POT3") (pin "2") (pintype "passive"))
      (node (ref "POT3") (pin "3") (pintype "passive"))
      (node (ref "U6") (pin "8") (pinfunction "RG_8") (pintype "passive"))
    )
    (net (code "91") (name "/RS") (class "Default")
      (node (ref "Pb") (pin "7") (pinfunction "7_7") (pintype "passive+no_connect"))
    )
    (net (code "92") (name "/SD-CLK") (class "Default")
      (node (ref "JP4") (pin "4") (pinfunction "4_4") (pintype "passive"))
      (node (ref "Pb") (pin "5") (pinfunction "5_5") (pintype "passive"))
    )
    (net (code "93") (name "/SD-DI") (class "Default")
      (node (ref "JP4") (pin "3") (pinfunction "3_3") (pintype "passive"))
      (node (ref "Pd") (pin "9") (pinfunction "9_9") (pintype "passive"))
    )
    (net (code "94") (name "/SD-DO") (class "Default")
      (node (ref "JP4") (pin "2") (pinfunction "2_2") (pintype "passive"))
      (node (ref "Pd") (pin "8") (pinfunction "8_8") (pintype "passive"))
    )
    (net (code "95") (name "/SWCLK") (class "Default")
      (node (ref "Pd") (pin "1") (pinfunction "1_1") (pintype "passive+no_connect"))
    )
    (net (code "96") (name "/SWDIO") (class "Default")
      (node (ref "Pc") (pin "14") (pinfunction "14_14") (pintype "passive+no_connect"))
    )
    (net (code "97") (name "/USART1-RX") (class "Default")
      (node (ref "JP6") (pin "3") (pinfunction "3_3") (pintype "passive"))
      (node (ref "Pd") (pin "11") (pinfunction "11_11") (pintype "passive"))
    )
    (net (code "98") (name "/USART1-TX") (class "Default")
      (node (ref "JP6") (pin "1") (pinfunction "1_1") (pintype "passive"))
      (node (ref "Pd") (pin "10") (pinfunction "10_10") (pintype "passive"))
    )
    (net (code "99") (name "/VDDA") (class "Default")
      (node (ref "Pa") (pin "13") (pinfunction "13_13") (pintype "passive+no_connect"))
    )
    (net (code "100") (name "/VSN") (class "Default")
      (node (ref "JP3a") (pin "1") (pinfunction "1_1") (pintype "passive"))
      (node (ref "R7") (pin "1") (pintype "passive"))
    )
    (net (code "101") (name "/VSP") (class "Default")
      (node (ref "JP3a") (pin "3") (pinfunction "3_3") (pintype "passive"))
      (node (ref "R8") (pin "1") (pintype "passive"))
    )
    (net (code "102") (name "/V_BAT") (class "Default")
      (node (ref "Pa") (pin "1") (pinfunction "1_1") (pintype "passive+no_connect"))
    )
    (net (code "103") (name "AGND") (class "Default")
      (node (ref "C10") (pin "2") (pintype "passive"))
      (node (ref "C11") (pin "2") (pintype "passive"))
      (node (ref "C12") (pin "2") (pintype "passive"))
      (node (ref "C14") (pin "2") (pintype "passive"))
      (node (ref "C15") (pin "1") (pintype "passive"))
      (node (ref "C16") (pin "2") (pintype "passive"))
      (node (ref "C17") (pin "2") (pintype "passive"))
      (node (ref "C18") (pin "2") (pintype "passive"))
      (node (ref "C19") (pin "2") (pintype "passive"))
      (node (ref "C20") (pin "2") (pintype "passive"))
      (node (ref "C21") (pin "2") (pintype "passive"))
      (node (ref "C22") (pin "2") (pintype "passive"))
      (node (ref "C23") (pin "2") (pintype "passive"))
      (node (ref "C24") (pin "2") (pintype "passive"))
      (node (ref "C5") (pin "2") (pintype "passive"))
      (node (ref "C7") (pin "2") (pintype "passive"))
      (node (ref "C8") (pin "1") (pintype "passive"))
      (node (ref "C9") (pin "2") (pintype "passive"))
      (node (ref "CE10") (pin "2") (pintype "passive"))
      (node (ref "CE11") (pin "1") (pintype "passive"))
      (node (ref "CE12") (pin "2") (pintype "passive"))
      (node (ref "CE13") (pin "2") (pintype "passive"))
      (node (ref "CE14") (pin "2") (pintype "passive"))
      (node (ref "CE15") (pin "2") (pintype "passive"))
      (node (ref "CE16") (pin "2") (pintype "passive"))
      (node (ref "CE17") (pin "2") (pintype "passive"))
      (node (ref "CE18") (pin "1") (pintype "passive"))
      (node (ref "CE19") (pin "1") (pintype "passive"))
      (node (ref "CE6") (pin "2") (pintype "passive"))
      (node (ref "CE7") (pin "1") (pintype "passive"))
      (node (ref "CE8") (pin "2") (pintype "passive"))
      (node (ref "CE9") (pin "1") (pintype "passive"))
      (node (ref "DZ1") (pin "1") (pinfunction "A_1") (pintype "passive"))
      (node (ref "DZ2") (pin "1") (pinfunction "A_1") (pintype "passive"))
      (node (ref "JP10") (pin "8") (pinfunction "8_8") (pintype "passive"))
      (node (ref "JP11") (pin "2") (pinfunction "2_2") (pintype "passive"))
      (node (ref "JP11") (pin "3") (pinfunction "3_3") (pintype "passive"))
      (node (ref "JP2") (pin "2") (pinfunction "2_2") (pintype "passive"))
      (node (ref "JP3a") (pin "2") (pinfunction "2_2") (pintype "passive"))
      (node (ref "JP3b") (pin "2") (pinfunction "2_2") (pintype "passive"))
      (node (ref "Pa") (pin "12") (pinfunction "12_12") (pintype "passive"))
      (node (ref "Pa") (pin "6") (pinfunction "6_6") (pintype "passive"))
      (node (ref "R20") (pin "1") (pintype "passive"))
      (node (ref "R24") (pin "1") (pintype "passive"))
      (node (ref "R28") (pin "1") (pintype "passive"))
      (node (ref "R32") (pin "1") (pintype "passive"))
      (node (ref "R36") (pin "1") (pintype "passive"))
      (node (ref "R40") (pin "1") (pintype "passive"))
      (node (ref "U3") (pin "1") (pintype "passive"))
      (node (ref "U4") (pin "2") (pintype "passive"))
    )
    (net (code "104") (name "Net-(C19-Pad1)") (class "Default")
      (node (ref "C19") (pin "1") (pintype "passive"))
      (node (ref "CE12") (pin "1") (pintype "passive"))
      (node (ref "R19") (pin "2") (pintype "passive"))
      (node (ref "R20") (pin "2") (pintype "passive"))
      (node (ref "R21") (pin "1") (pintype "passive"))
      (node (ref "R22") (pin "2") (pintype "passive"))
    )
    (net (code "105") (name "Net-(C20-Pad1)") (class "Default")
      (node (ref "C20") (pin "1") (pintype "passive"))
      (node (ref "CE13") (pin "1") (pintype "passive"))
      (node (ref "R23") (pin "2") (pintype "passive"))
      (node (ref "R24") (pin "2") (pintype "passive"))
      (node (ref "R25") (pin "1") (pintype "passive"))
      (node (ref "R26") (pin "2") (pintype "passive"))
    )
    (net (code "106") (name "Net-(C21-Pad1)") (class "Default")
      (node (ref "C21") (pin "1") (pintype "passive"))
      (node (ref "CE14") (pin "1") (pintype "passive"))
      (node (ref "R27") (pin "2") (pintype "passive"))
      (node (ref "R28") (pin "2") (pintype "passive"))
      (node (ref "R29") (pin "1") (pintype "passive"))
      (node (ref "R30") (pin "2") (pintype "passive"))
    )
    (net (code "107") (name "Net-(C22-Pad1)") (class "Default")
      (node (ref "C22") (pin "1") (pintype "passive"))
      (node (ref "CE15") (pin "1") (pintype "passive"))
      (node (ref "R31") (pin "2") (pintype "passive"))
      (node (ref "R32") (pin "2") (pintype "passive"))
      (node (ref "R33") (pin "1") (pintype "passive"))
      (node (ref "R34") (pin "2") (pintype "passive"))
    )
    (net (code "108") (name "Net-(C23-Pad1)") (class "Default")
      (node (ref "C23") (pin "1") (pintype "passive"))
      (node (ref "CE16") (pin "1") (pintype "passive"))
      (node (ref "R35") (pin "2") (pintype "passive"))
      (node (ref "R36") (pin "2") (pintype "passive"))
      (node (ref "R37") (pin "1") (pintype "passive"))
      (node (ref "R38") (pin "2") (pintype "passive"))
    )
    (net (code "109") (name "Net-(C24-Pad1)") (class "Default")
      (node (ref "C24") (pin "1") (pintype "passive"))
      (node (ref "CE17") (pin "1") (pintype "passive"))
      (node (ref "R39") (pin "2") (pintype "passive"))
      (node (ref "R40") (pin "2") (pintype "passive"))
      (node (ref "R41") (pin "1") (pintype "passive"))
      (node (ref "R42") (pin "2") (pintype "passive"))
    )
    (net (code "110") (name "Net-(D2-A)") (class "Default")
      (node (ref "C1") (pin "2") (pintype "passive"))
      (node (ref "C3") (pin "2") (pintype "passive"))
      (node (ref "CE1") (pin "2") (pintype "passive"))
      (node (ref "CE2") (pin "2") (pintype "passive"))
      (node (ref "D2") (pin "1") (pinfunction "A_1") (pintype "passive"))
      (node (ref "LED1") (pin "2") (pinfunction "K_2") (pintype "passive"))
      (node (ref "R1") (pin "2") (pintype "passive"))
      (node (ref "R2") (pin "2") (pintype "passive"))
      (node (ref "U1") (pin "3") (pinfunction "GND_3") (pintype "passive"))
    )
    (net (code "111") (name "Net-(D2-K)") (class "Default")
      (node (ref "D2") (pin "2") (pinfunction "K_2") (pintype "passive"))
      (node (ref "L1") (pin "2") (pinfunction "2_2") (pintype "passive"))
      (node (ref "U1") (pin "2") (pinfunction "OUT_2") (pintype "passive"))
    )
    (net (code "112") (name "Net-(LED1-A)") (class "Default")
      (node (ref "LED1") (pin "1") (pinfunction "A_1") (pintype "passive"))
      (node (ref "R4") (pin "2") (pintype "passive"))
    )
    (net (code "113") (name "Net-(OP1-K)") (class "Default")
      (node (ref "OP1") (pin "2") (pinfunction "K_2") (pintype "passive"))
      (node (ref "R70") (pin "2") (pintype "passive"))
    )
    (net (code "114") (name "Net-(OP2-K)") (class "Default")
      (node (ref "OP2") (pin "2") (pinfunction "K_2") (pintype "passive"))
      (node (ref "R72") (pin "2") (pintype "passive"))
    )
    (net (code "115") (name "Net-(OP3-K)") (class "Default")
      (node (ref "OP3") (pin "2") (pinfunction "K_2") (pintype "passive"))
      (node (ref "R74") (pin "2") (pintype "passive"))
    )
    (net (code "116") (name "Net-(OP4-K)") (class "Default")
      (node (ref "OP4") (pin "2") (pinfunction "K_2") (pintype "passive"))
      (node (ref "R76") (pin "2") (pintype "passive"))
    )
    (net (code "117") (name "Net-(POT1-Pad1)") (class "Default")
      (node (ref "POT1") (pin "1") (pintype "passive"))
      (node (ref "R9") (pin "2") (pintype "passive"))
    )
    (net (code "118") (name "Net-(POT2-Pad1)") (class "Default")
      (node (ref "POT2") (pin "1") (pintype "passive"))
      (node (ref "R11") (pin "2") (pintype "passive"))
    )
    (net (code "119") (name "Net-(POT2-Pad2)") (class "Default")
      (node (ref "POT2") (pin "2") (pintype "passive"))
      (node (ref "R12") (pin "1") (pintype "passive"))
    )
    (net (code "120") (name "Net-(POT3-Pad1)") (class "Default")
      (node (ref "POT3") (pin "1") (pintype "passive"))
      (node (ref "R15") (pin "2") (pintype "passive"))
    )
    (net (code "121") (name "Net-(POT4-Pad1)") (class "Default")
      (node (ref "POT4") (pin "1") (pintype "passive"))
      (node (ref "R17") (pin "2") (pintype "passive"))
    )
    (net (code "122") (name "Net-(POT4-Pad2)") (class "Default")
      (node (ref "POT4") (pin "2") (pintype "passive"))
      (node (ref "R18") (pin "1") (pintype "passive"))
    )
    (net (code "123") (name "Net-(Q1-B)") (class "Default")
      (node (ref "Q1") (pin "1") (pinfunction "B_1") (pintype "passive"))
      (node (ref "R43") (pin "2") (pintype "passive"))
      (node (ref "R44") (pin "1") (pintype "passive"))
    )
    (net (code "124") (name "Net-(Q1-C)") (class "Default")
      (node (ref "Q1") (pin "3") (pinfunction "C_3") (pintype "passive"))
      (node (ref "R45") (pin "1") (pintype "passive"))
    )
    (net (code "125") (name "Net-(Q2-B)") (class "Default")
      (node (ref "Q2") (pin "1") (pinfunction "B_1") (pintype "passive"))
      (node (ref "R46") (pin "2") (pintype "passive"))
      (node (ref "R47") (pin "1") (pintype "passive"))
    )
    (net (code "126") (name "Net-(Q2-C)") (class "Default")
      (node (ref "Q2") (pin "3") (pinfunction "C_3") (pintype "passive"))
      (node (ref "R48") (pin "1") (pintype "passive"))
    )
    (net (code "127") (name "Net-(Q3-B)") (class "Default")
      (node (ref "Q3") (pin "1") (pinfunction "B_1") (pintype "passive"))
      (node (ref "R49") (pin "2") (pintype "passive"))
      (node (ref "R50") (pin "1") (pintype "passive"))
    )
    (net (code "128") (name "Net-(Q3-C)") (class "Default")
      (node (ref "Q3") (pin "3") (pinfunction "C_3") (pintype "passive"))
      (node (ref "R51") (pin "1") (pintype "passive"))
    )
    (net (code "129") (name "Net-(Q4-B)") (class "Default")
      (node (ref "Q4") (pin "1") (pinfunction "B_1") (pintype "passive"))
      (node (ref "R52") (pin "2") (pintype "passive"))
      (node (ref "R53") (pin "1") (pintype "passive"))
    )
    (net (code "130") (name "Net-(Q4-C)") (class "Default")
      (node (ref "Q4") (pin "3") (pinfunction "C_3") (pintype "passive"))
      (node (ref "R54") (pin "1") (pintype "passive"))
    )
    (net (code "131") (name "Net-(Q5-B)") (class "Default")
      (node (ref "Q5") (pin "1") (pinfunction "B_1") (pintype "passive"))
      (node (ref "R55") (pin "2") (pintype "passive"))
      (node (ref "R56") (pin "1") (pintype "passive"))
    )
    (net (code "132") (name "Net-(Q5-C)") (class "Default")
      (node (ref "Q5") (pin "3") (pinfunction "C_3") (pintype "passive"))
      (node (ref "R57") (pin "1") (pintype "passive"))
    )
    (net (code "133") (name "Net-(Q6-B)") (class "Default")
      (node (ref "Q6") (pin "1") (pinfunction "B_1") (pintype "passive"))
      (node (ref "R58") (pin "2") (pintype "passive"))
      (node (ref "R59") (pin "1") (pintype "passive"))
    )
    (net (code "134") (name "Net-(Q6-C)") (class "Default")
      (node (ref "Q6") (pin "3") (pinfunction "C_3") (pintype "passive"))
      (node (ref "R60") (pin "1") (pintype "passive"))
    )
    (net (code "135") (name "Net-(Q7-B)") (class "Default")
      (node (ref "Q7") (pin "1") (pinfunction "B_1") (pintype "passive"))
      (node (ref "R61") (pin "2") (pintype "passive"))
      (node (ref "R62") (pin "1") (pintype "passive"))
    )
    (net (code "136") (name "Net-(Q8-B)") (class "Default")
      (node (ref "Q8") (pin "1") (pinfunction "B_1") (pintype "passive"))
      (node (ref "R64") (pin "2") (pintype "passive"))
      (node (ref "R65") (pin "1") (pintype "passive"))
    )
    (net (code "137") (name "Net-(U1-!ON{slash}OFF)") (class "Default")
      (node (ref "C2") (pin "2") (pintype "passive"))
      (node (ref "R1") (pin "1") (pintype "passive"))
      (node (ref "U1") (pin "5") (pinfunction "!ON/OFF_5") (pintype "passive"))
    )
    (net (code "138") (name "Net-(U1-FeedBack)") (class "Default")
      (node (ref "R2") (pin "1") (pintype "passive"))
      (node (ref "R3") (pin "2") (pintype "passive"))
      (node (ref "U1") (pin "4") (pinfunction "FeedBack_4") (pintype "passive"))
    )
    (net (code "139") (name "Net-(U2-CAP+)") (class "Default")
      (node (ref "CE5") (pin "1") (pintype "passive"))
      (node (ref "U2") (pin "2") (pinfunction "CAP+_2") (pintype "passive"))
    )
    (net (code "140") (name "Net-(U2-CAP-)") (class "Default")
      (node (ref "CE5") (pin "2") (pintype "passive"))
      (node (ref "U2") (pin "4") (pinfunction "CAP-_4") (pintype "passive"))
    )
    (net (code "141") (name "Net-(U2-Vout)") (class "Default")
      (node (ref "CE4") (pin "2") (pintype "passive"))
      (node (ref "L2") (pin "1") (pinfunction "1_1") (pintype "passive"))
      (node (ref "U2") (pin "5") (pinfunction "Vout_5") (pintype "passive"))
    )
    (net (code "142") (name "Net-(U5-OUT)") (class "Default")
      (node (ref "R10") (pin "2") (pintype "passive"))
      (node (ref "U5") (pin "6") (pinfunction "OUT_6") (pintype "passive"))
    )
    (net (code "143") (name "Net-(U6-OUT)") (class "Default")
      (node (ref "R16") (pin "2") (pintype "passive"))
      (node (ref "U6") (pin "6") (pinfunction "OUT_6") (pintype "passive"))
    )
    (net (code "144") (name "unconnected-(M1-Pad1)") (class "Default")
      (node (ref "M1") (pin "1") (pinfunction "1_1") (pintype "passive+no_connect"))
    )
    (net (code "145") (name "unconnected-(M2-Pad1)") (class "Default")
      (node (ref "M2") (pin "1") (pinfunction "1_1") (pintype "passive+no_connect"))
    )
    (net (code "146") (name "unconnected-(M3-Pad1)") (class "Default")
      (node (ref "M3") (pin "1") (pinfunction "1_1") (pintype "passive+no_connect"))
    )
    (net (code "147") (name "unconnected-(M4-Pad1)") (class "Default")
      (node (ref "M4") (pin "1") (pinfunction "1_1") (pintype "passive+no_connect"))
    )
    (net (code "148") (name "unconnected-(M5-Pad1)") (class "Default")
      (node (ref "M5") (pin "1") (pinfunction "1_1") (pintype "passive+no_connect"))
    )
    (net (code "149") (name "unconnected-(M6-Pad1)") (class "Default")
      (node (ref "M6") (pin "1") (pinfunction "1_1") (pintype "passive+no_connect"))
    )
    (net (code "150") (name "unconnected-(M7-Pad1)") (class "Default")
      (node (ref "M7") (pin "1") (pinfunction "1_1") (pintype "passive+no_connect"))
    )
    (net (code "151") (name "unconnected-(OP1-B-Pad6)") (class "Default")
      (node (ref "OP1") (pin "6") (pinfunction "B_6") (pintype "passive"))
    )
    (net (code "152") (name "unconnected-(OP1-NC-Pad3)") (class "Default")
      (node (ref "OP1") (pin "3") (pinfunction "NC_3") (pintype "passive"))
    )
    (net (code "153") (name "unconnected-(OP2-B-Pad6)") (class "Default")
      (node (ref "OP2") (pin "6") (pinfunction "B_6") (pintype "passive"))
    )
    (net (code "154") (name "unconnected-(OP2-NC-Pad3)") (class "Default")
      (node (ref "OP2") (pin "3") (pinfunction "NC_3") (pintype "passive"))
    )
    (net (code "155") (name "unconnected-(OP3-B-Pad6)") (class "Default")
      (node (ref "OP3") (pin "6") (pinfunction "B_6") (pintype "passive"))
    )
    (net (code "156") (name "unconnected-(OP3-NC-Pad3)") (class "Default")
      (node (ref "OP3") (pin "3") (pinfunction "NC_3") (pintype "passive"))
    )
    (net (code "157") (name "unconnected-(OP4-B-Pad6)") (class "Default")
      (node (ref "OP4") (pin "6") (pinfunction "B_6") (pintype "passive"))
    )
    (net (code "158") (name "unconnected-(OP4-NC-Pad3)") (class "Default")
      (node (ref "OP4") (pin "3") (pinfunction "NC_3") (pintype "passive"))
    )
    (net (code "159") (name "unconnected-(Pa-Pad7)") (class "Default")
      (node (ref "Pa") (pin "7") (pinfunction "7_7") (pintype "passive"))
    )
    (net (code "160") (name "unconnected-(Pd-Pad12)") (class "Default")
      (node (ref "Pd") (pin "12") (pinfunction "12_12") (pintype "passive+no_connect"))
    )
    (net (code "161") (name "unconnected-(U2-LV-Pad6)") (class "Default")
      (node (ref "U2") (pin "6") (pinfunction "LV_6") (pintype "passive"))
    )
    (net (code "162") (name "unconnected-(U2-OSC-Pad7)") (class "Default")
      (node (ref "U2") (pin "7") (pinfunction "OSC_7") (pintype "passive"))
    )
    (net (code "163") (name "unconnected-(U2-TEST-Pad1)") (class "Default")
      (node (ref "U2") (pin "1") (pinfunction "TEST_1") (pintype "passive"))
    )
    (net (code "164") (name "unconnected-(U3-Pad3)") (class "Default")
      (node (ref "U3") (pin "3") (pintype "passive+no_connect"))
    )
    (net (code "165") (name "unconnected-(U4-Pad3)") (class "Default")
      (node (ref "U4") (pin "3") (pintype "passive+no_connect"))
    )
  )
)
